# CZ201C_V2_0.net
KiCad netlist of a schematic drawn in Altium Designer
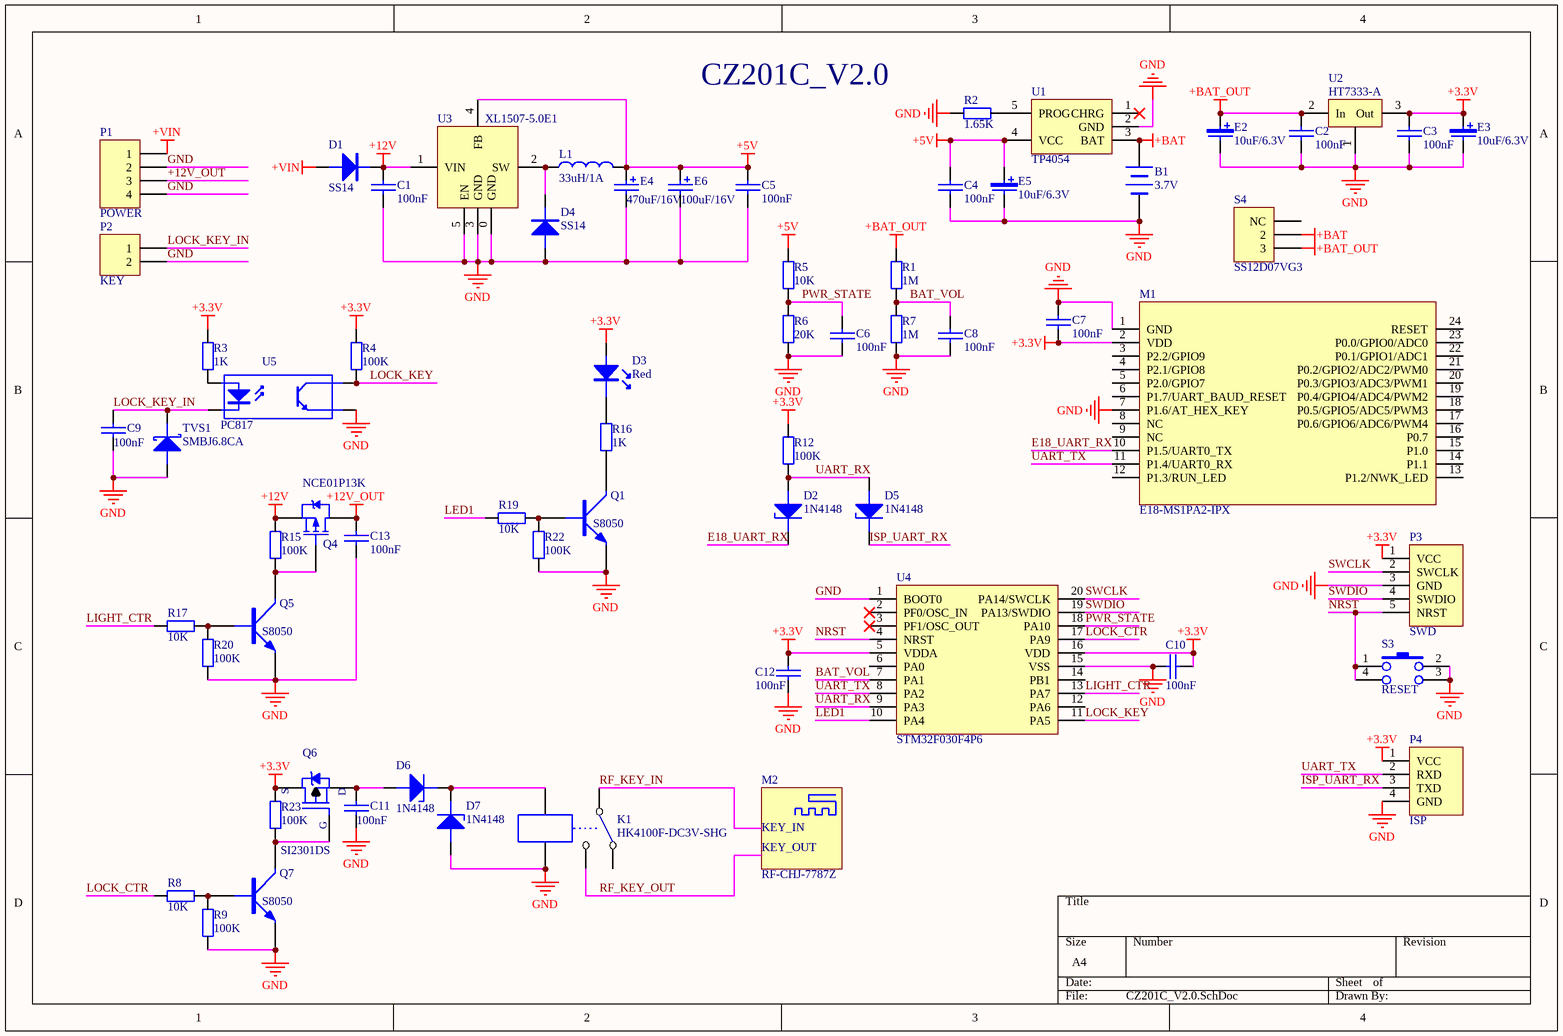
[diagram p0: CZ201C_V2.0.SchDoc]

(export (version "E")
  (design (tool "Eeschema 10.0.6"))
  (components
    (comp (ref "B1")
      (value "3.7V")
      (footprint "Cheng_Interface Unit:XH2.54-2P-BAT")
      (libsource (lib "Cheng_Misc Component") (part "BATTERY"))
    )
    (comp (ref "C1")
      (value "100nF")
      (footprint "Cheng_Resistor_Capacitor:0603_CN")
      (libsource (lib "Cheng_Resistor_Capacitor") (part "Cap1"))
    )
    (comp (ref "C2")
      (value "100nF")
      (footprint "Cheng_Resistor_Capacitor:0603_CN")
      (libsource (lib "Cheng_Resistor_Capacitor") (part "Cap1"))
    )
    (comp (ref "C3")
      (value "100nF")
      (footprint "Cheng_Resistor_Capacitor:0603_CN")
      (libsource (lib "Cheng_Resistor_Capacitor") (part "Cap1"))
    )
    (comp (ref "C4")
      (value "100nF")
      (footprint "Cheng_Resistor_Capacitor:0603_CN")
      (libsource (lib "Cheng_Resistor_Capacitor") (part "Cap1"))
    )
    (comp (ref "C5")
      (value "100nF")
      (footprint "Cheng_Resistor_Capacitor:0603_CN")
      (libsource (lib "Cheng_Resistor_Capacitor") (part "Cap1"))
    )
    (comp (ref "C6")
      (value "100nF")
      (footprint "Cheng_Resistor_Capacitor:0603_CN")
      (libsource (lib "Cheng_Resistor_Capacitor") (part "Cap1"))
    )
    (comp (ref "C7")
      (value "100nF")
      (footprint "Cheng_Resistor_Capacitor:0603_CN")
      (libsource (lib "Cheng_Resistor_Capacitor") (part "Cap1"))
    )
    (comp (ref "C8")
      (value "100nF")
      (footprint "Cheng_Resistor_Capacitor:0603_CN")
      (libsource (lib "Cheng_Resistor_Capacitor") (part "Cap1"))
    )
    (comp (ref "C9")
      (value "100nF")
      (footprint "Cheng_Resistor_Capacitor:0603_CN")
      (libsource (lib "Cheng_Resistor_Capacitor") (part "Cap1"))
    )
    (comp (ref "C10")
      (value "100nF")
      (footprint "Cheng_Resistor_Capacitor:0603_CN")
      (libsource (lib "Cheng_Resistor_Capacitor") (part "Cap1"))
    )
    (comp (ref "C11")
      (value "100nF")
      (footprint "Cheng_Resistor_Capacitor:0603_CN")
      (libsource (lib "Cheng_Resistor_Capacitor") (part "Cap1"))
    )
    (comp (ref "C12")
      (value "100nF")
      (footprint "Cheng_Resistor_Capacitor:0603_CN")
      (libsource (lib "Cheng_Resistor_Capacitor") (part "Cap1"))
    )
    (comp (ref "C13")
      (value "100nF")
      (footprint "Cheng_Resistor_Capacitor:0603_CN")
      (libsource (lib "Cheng_Resistor_Capacitor") (part "Cap1"))
    )
    (comp (ref "D1")
      (value "SS14")
      (footprint "Cheng_Diode_Transistor:DO-214AC(SMA)")
      (libsource (lib "Cheng_Diode_Transistor") (part "Diode-A"))
    )
    (comp (ref "D2")
      (value "1N4148")
      (footprint "Cheng_Diode_Transistor:LL-34")
      (libsource (lib "Cheng_Diode_Transistor") (part "Diode-B"))
    )
    (comp (ref "D3")
      (value "Red")
      (footprint "Cheng_Diode_Transistor:0603_LED")
      (libsource (lib "Cheng_Diode_Transistor") (part "LED"))
    )
    (comp (ref "D4")
      (value "SS14")
      (footprint "Cheng_Diode_Transistor:DO-214AC(SMA)")
      (libsource (lib "Cheng_Diode_Transistor") (part "Diode-A"))
    )
    (comp (ref "D5")
      (value "1N4148")
      (footprint "Cheng_Diode_Transistor:LL-34")
      (libsource (lib "Cheng_Diode_Transistor") (part "Diode-B"))
    )
    (comp (ref "D6")
      (value "1N4148")
      (footprint "Cheng_Diode_Transistor:LL-34")
      (libsource (lib "Cheng_Diode_Transistor") (part "Diode-B"))
    )
    (comp (ref "D7")
      (value "1N4148")
      (footprint "Cheng_Diode_Transistor:LL-34")
      (libsource (lib "Cheng_Diode_Transistor") (part "Diode-B"))
    )
    (comp (ref "E2")
      (value "10uF/6.3V")
      (footprint "Cheng_Resistor_Capacitor:3216_E")
      (libsource (lib "Cheng_Resistor_Capacitor") (part "Cap Ta"))
    )
    (comp (ref "E3")
      (value "10uF/6.3V")
      (footprint "Cheng_Resistor_Capacitor:3216_E")
      (libsource (lib "Cheng_Resistor_Capacitor") (part "Cap Ta"))
    )
    (comp (ref "E4")
      (value "470uF/16V")
      (footprint "Cheng_Resistor_Capacitor:CS_470uF/16V")
      (libsource (lib "Cheng_Resistor_Capacitor") (part "Cap Pol1"))
    )
    (comp (ref "E5")
      (value "10uF/6.3V")
      (footprint "Cheng_Resistor_Capacitor:3216_E")
      (libsource (lib "Cheng_Resistor_Capacitor") (part "Cap Ta"))
    )
    (comp (ref "E6")
      (value "100uF/16V")
      (footprint "Cheng_Resistor_Capacitor:CS_100uF/16V")
      (libsource (lib "Cheng_Resistor_Capacitor") (part "Cap Pol1"))
    )
    (comp (ref "K1")
      (value "HK4100F-DC3V-SHG")
      (footprint "Cheng_Misc Component:HK4100-DC5V-SHG")
      (description "HK4100-DC5V-SHG,HRS1H-S-DC5V")
      (libsource (lib "Cheng_Misc Component") (part "HK4100F-DC5V-SHG"))
    )
    (comp (ref "L1")
      (value "33uH/1A")
      (footprint "Cheng_Resistor_Capacitor:CDRH74")
      (libsource (lib "Cheng_Resistor_Capacitor") (part "Inductor"))
    )
    (comp (ref "M1")
      (value "E18-MS1PA2-IPX")
      (footprint "Cheng_Module:E18-MS1PA2-IPX")
      (libsource (lib "Cheng_Module") (part "E18-MS1PA2-IPX"))
    )
    (comp (ref "M2")
      (value "RF-CHJ-7787Z")
      (footprint "Cheng_Module:RF-CHJ-7787Z")
      (libsource (lib "Cheng_Module") (part "RF-CHJ-7787Z"))
    )
    (comp (ref "P1")
      (value "POWER")
      (footprint "Cheng_Interface Unit:KF3.5-4P")
      (description "Header, 4-Pin")
      (fields (field (name "PUBLISHER") "Altium Limited"))
      (libsource (lib "Cheng_Interface Unit") (part "Header 4"))
    )
    (comp (ref "P2")
      (value "KEY")
      (footprint "Cheng_Interface Unit:KF3.5-2P")
      (description "Header, 2-Pin")
      (fields (field (name "PUBLISHER") "Altium Limited"))
      (libsource (lib "Cheng_Interface Unit") (part "Header 2"))
    )
    (comp (ref "P3")
      (value "SWD")
      (footprint "Cheng_Interface Unit:XH2.54-5P")
      (libsource (lib "Cheng_Interface Unit") (part "SWD"))
    )
    (comp (ref "P4")
      (value "ISP")
      (footprint "Cheng_Interface Unit:XH2.54-4P")
      (libsource (lib "Cheng_Interface Unit") (part "ISP_UART"))
    )
    (comp (ref "Q1")
      (value "S8050")
      (footprint "Cheng_Diode_Transistor:SOT-23")
      (libsource (lib "Cheng_Diode_Transistor") (part "8050"))
    )
    (comp (ref "Q4")
      (value "NCE01P13K")
      (footprint "Cheng_Manostat:TO-252")
      (description "P-Channel Power MOSFET")
      (fields (field (name "PUBLISHER") "Altium Limited"))
      (libsource (lib "Miscellaneous Devices") (part "PMOS-2"))
    )
    (comp (ref "Q5")
      (value "S8050")
      (footprint "Cheng_Diode_Transistor:SOT-23")
      (libsource (lib "Cheng_Diode_Transistor") (part "8050"))
    )
    (comp (ref "Q6")
      (value "SI2301DS")
      (footprint "Cheng_Diode_Transistor:SOT-23")
      (libsource (lib "Cheng_Diode_Transistor") (part "MOSFET P"))
    )
    (comp (ref "Q7")
      (value "S8050")
      (footprint "Cheng_Diode_Transistor:SOT-23")
      (libsource (lib "Cheng_Diode_Transistor") (part "8050"))
    )
    (comp (ref "R1")
      (value "1M")
      (footprint "Cheng_Resistor_Capacitor:0603_RN")
      (libsource (lib "") (part "Res1_1"))
    )
    (comp (ref "R2")
      (value "1.65K")
      (footprint "Cheng_Resistor_Capacitor:0603_RN")
      (libsource (lib "Cheng_Resistor_Capacitor") (part "Res1"))
    )
    (comp (ref "R3")
      (value "1K")
      (footprint "Cheng_Resistor_Capacitor:0603_RN")
      (libsource (lib "") (part "Res1_1"))
    )
    (comp (ref "R4")
      (value "100K")
      (footprint "Cheng_Resistor_Capacitor:0603_RN")
      (libsource (lib "") (part "Res1_1"))
    )
    (comp (ref "R5")
      (value "10K")
      (footprint "Cheng_Resistor_Capacitor:0603_RN")
      (libsource (lib "") (part "Res1_1"))
    )
    (comp (ref "R6")
      (value "20K")
      (footprint "Cheng_Resistor_Capacitor:0603_RN")
      (libsource (lib "") (part "Res1_1"))
    )
    (comp (ref "R7")
      (value "1M")
      (footprint "Cheng_Resistor_Capacitor:0603_RN")
      (libsource (lib "") (part "Res1_1"))
    )
    (comp (ref "R8")
      (value "10K")
      (footprint "Cheng_Resistor_Capacitor:0603_RN")
      (libsource (lib "") (part "Res1_2"))
    )
    (comp (ref "R9")
      (value "100K")
      (footprint "Cheng_Resistor_Capacitor:0603_RN")
      (libsource (lib "") (part "Res1_1"))
    )
    (comp (ref "R12")
      (value "100K")
      (footprint "Cheng_Resistor_Capacitor:0603_RN")
      (libsource (lib "") (part "Res1_1"))
    )
    (comp (ref "R15")
      (value "100K")
      (footprint "Cheng_Resistor_Capacitor:0603_RN")
      (libsource (lib "") (part "Res1_1"))
    )
    (comp (ref "R16")
      (value "1K")
      (footprint "Cheng_Resistor_Capacitor:0603_RN")
      (libsource (lib "") (part "Res1_1"))
    )
    (comp (ref "R17")
      (value "10K")
      (footprint "Cheng_Resistor_Capacitor:0603_RN")
      (libsource (lib "Cheng_Resistor_Capacitor") (part "Res1"))
    )
    (comp (ref "R19")
      (value "10K")
      (footprint "Cheng_Resistor_Capacitor:0603_RN")
      (libsource (lib "") (part "Res1_2"))
    )
    (comp (ref "R20")
      (value "100K")
      (footprint "Cheng_Resistor_Capacitor:0603_RN")
      (libsource (lib "") (part "Res1_1"))
    )
    (comp (ref "R22")
      (value "100K")
      (footprint "Cheng_Resistor_Capacitor:0603_RN")
      (libsource (lib "") (part "Res1_1"))
    )
    (comp (ref "R23")
      (value "100K")
      (footprint "Cheng_Resistor_Capacitor:0603_RN")
      (libsource (lib "") (part "Res1_1"))
    )
    (comp (ref "S3")
      (value "RESET")
      (footprint "Cheng_Misc Component:KEY-6*6MM-DIP")
      (libsource (lib "Cheng_Misc Component") (part "SW-4"))
    )
    (comp (ref "S4")
      (value "SS12D07VG3")
      (footprint "Cheng_Misc Component:SS-12D07G3")
      (libsource (lib "Cheng_Misc Component") (part "SS-12D07G3"))
    )
    (comp (ref "TVS1")
      (value "SMBJ6.8CA")
      (footprint "Cheng_Diode_Transistor:DO-214AA(SMB)")
      (libsource (lib "Cheng_Diode_Transistor") (part "Diode-C"))
    )
    (comp (ref "U1")
      (value "TP4054")
      (footprint "Cheng_Diode_Transistor:SOT-23-5")
      (description "TP4054,LTC4054 ,PJ4054MR")
      (libsource (lib "Cheng_IC") (part "QX4054"))
    )
    (comp (ref "U2")
      (value "HT7333-A")
      (footprint "SOT-89")
      (description "HT7533; Output 500mA; Iq: 5uA, max= 7uA")
      (libsource (lib "Cheng_Manostat") (part "HT7833"))
    )
    (comp (ref "U3")
      (value "XL1507-5.0E1")
      (footprint "Cheng_Manostat:TO-252-5")
      (libsource (lib "Cheng_Manostat") (part "XL1507"))
    )
    (comp (ref "U4")
      (value "STM32F030F4P6")
      (footprint "Cheng_IC:TSSOP20")
      (libsource (lib "Cheng_STM32") (part "STM32F030F4P6"))
    )
    (comp (ref "U5")
      (value "PC817")
      (footprint "Cheng_IC:SOP-4")
      (libsource (lib "Cheng_Diode_Transistor") (part "PC817"))
    )
  )
  (nets
    (net (code "1") (name "+3.3V") (class "Default")
      (node (ref "C10") (pin "1") (pinfunction "1_1") (pintype "passive"))
      (node (ref "C12") (pin "1") (pinfunction "1_1") (pintype "passive"))
      (node (ref "C3") (pin "1") (pinfunction "1_1") (pintype "passive"))
      (node (ref "C7") (pin "2") (pinfunction "2_2") (pintype "passive"))
      (node (ref "D3") (pin "A") (pinfunction "1_A") (pintype "passive"))
      (node (ref "E3") (pin "1") (pinfunction "1_1") (pintype "passive"))
      (node (ref "M1") (pin "2") (pinfunction "VDD_2") (pintype "passive"))
      (node (ref "P3") (pin "1") (pinfunction "VCC_1") (pintype "passive"))
      (node (ref "P4") (pin "1") (pinfunction "VCC_1") (pintype "passive"))
      (node (ref "Q6") (pin "2") (pinfunction "S_2") (pintype "passive"))
      (node (ref "R12") (pin "2") (pinfunction "2_2") (pintype "passive"))
      (node (ref "R23") (pin "2") (pinfunction "2_2") (pintype "passive"))
      (node (ref "R3") (pin "2") (pinfunction "2_2") (pintype "passive"))
      (node (ref "R4") (pin "2") (pinfunction "2_2") (pintype "passive"))
      (node (ref "U2") (pin "3") (pinfunction "Out_3") (pintype "passive"))
      (node (ref "U4") (pin "16") (pinfunction "VDD_16") (pintype "passive"))
      (node (ref "U4") (pin "5") (pinfunction "VDDA_5") (pintype "passive"))
    )
    (net (code "2") (name "+5V") (class "Default")
      (node (ref "C4") (pin "1") (pinfunction "1_1") (pintype "passive"))
      (node (ref "C5") (pin "1") (pinfunction "1_1") (pintype "passive"))
      (node (ref "E4") (pin "1") (pinfunction "1_1") (pintype "passive"))
      (node (ref "E5") (pin "1") (pinfunction "1_1") (pintype "passive"))
      (node (ref "E6") (pin "1") (pinfunction "1_1") (pintype "passive"))
      (node (ref "L1") (pin "2") (pinfunction "2_2") (pintype "passive"))
      (node (ref "R5") (pin "2") (pinfunction "2_2") (pintype "passive"))
      (node (ref "U1") (pin "4") (pinfunction "VCC_4") (pintype "power_in"))
      (node (ref "U3") (pin "4") (pinfunction "FB_4") (pintype "passive"))
    )
    (net (code "3") (name "+12V") (class "Default")
      (node (ref "C1") (pin "1") (pinfunction "1_1") (pintype "passive"))
      (node (ref "D1") (pin "K") (pinfunction "2_K") (pintype "passive"))
      (node (ref "Q4") (pin "3") (pinfunction "S_3") (pintype "passive"))
      (node (ref "R15") (pin "2") (pinfunction "2_2") (pintype "passive"))
      (node (ref "U3") (pin "1") (pinfunction "VIN_1") (pintype "passive"))
    )
    (net (code "4") (name "+12V_OUT") (class "Default")
      (node (ref "C13") (pin "1") (pinfunction "1_1") (pintype "passive"))
      (node (ref "P1") (pin "3") (pinfunction "3_3") (pintype "passive"))
      (node (ref "Q4") (pin "2") (pinfunction "D_2") (pintype "passive"))
    )
    (net (code "5") (name "+BAT") (class "Default")
      (node (ref "B1") (pin "1") (pinfunction "+_1") (pintype "passive"))
      (node (ref "S4") (pin "2") (pinfunction "2_2") (pintype "passive"))
      (node (ref "U1") (pin "3") (pinfunction "BAT_3") (pintype "passive"))
    )
    (net (code "6") (name "+BAT_OUT") (class "Default")
      (node (ref "C2") (pin "1") (pinfunction "1_1") (pintype "passive"))
      (node (ref "E2") (pin "1") (pinfunction "1_1") (pintype "passive"))
      (node (ref "R1") (pin "2") (pinfunction "2_2") (pintype "passive"))
      (node (ref "S4") (pin "3") (pinfunction "3_3") (pintype "passive"))
      (node (ref "U2") (pin "2") (pinfunction "In_2") (pintype "passive"))
    )
    (net (code "7") (name "+VIN") (class "Default")
      (node (ref "D1") (pin "A") (pinfunction "1_A") (pintype "passive"))
      (node (ref "P1") (pin "1") (pinfunction "1_1") (pintype "passive"))
    )
    (net (code "8") (name "/BAT_VOL") (class "Default")
      (node (ref "C8") (pin "1") (pinfunction "1_1") (pintype "passive"))
      (node (ref "R1") (pin "1") (pinfunction "1_1") (pintype "passive"))
      (node (ref "R7") (pin "2") (pinfunction "2_2") (pintype "passive"))
      (node (ref "U4") (pin "7") (pinfunction "PA1_7") (pintype "passive"))
    )
    (net (code "9") (name "/E18_UART_RX") (class "Default")
      (node (ref "D2") (pin "K") (pinfunction "2_K") (pintype "passive"))
      (node (ref "M1") (pin "10") (pinfunction "P1.5/UART0_TX_10") (pintype "passive"))
    )
    (net (code "10") (name "/ISP_UART_RX") (class "Default")
      (node (ref "D5") (pin "K") (pinfunction "2_K") (pintype "passive"))
      (node (ref "P4") (pin "3") (pinfunction "TXD_3") (pintype "passive"))
    )
    (net (code "11") (name "/LED1") (class "Default")
      (node (ref "R19") (pin "2") (pinfunction "2_2") (pintype "passive"))
      (node (ref "U4") (pin "10") (pinfunction "PA4_10") (pintype "passive"))
    )
    (net (code "12") (name "/LIGHT_CTR") (class "Default")
      (node (ref "R17") (pin "1") (pinfunction "1_1") (pintype "passive"))
      (node (ref "U4") (pin "13") (pinfunction "PA7_13") (pintype "passive"))
    )
    (net (code "13") (name "/LOCK_CTR") (class "Default")
      (node (ref "R8") (pin "2") (pinfunction "2_2") (pintype "passive"))
      (node (ref "U4") (pin "17") (pinfunction "PA9_17") (pintype "passive"))
    )
    (net (code "14") (name "/LOCK_KEY") (class "Default")
      (node (ref "R4") (pin "1") (pinfunction "1_1") (pintype "passive"))
      (node (ref "U4") (pin "11") (pinfunction "PA5_11") (pintype "passive"))
      (node (ref "U5") (pin "4") (pinfunction "C_4") (pintype "passive"))
    )
    (net (code "15") (name "/LOCK_KEY_IN") (class "Default")
      (node (ref "C9") (pin "1") (pinfunction "1_1") (pintype "passive"))
      (node (ref "P2") (pin "1") (pinfunction "1_1") (pintype "passive"))
      (node (ref "TVS1") (pin "K") (pinfunction "2_K") (pintype "passive"))
      (node (ref "U5") (pin "2") (pinfunction "K_2") (pintype "passive"))
    )
    (net (code "16") (name "/NRST") (class "Default")
      (node (ref "P3") (pin "5") (pinfunction "NRST_5") (pintype "passive"))
      (node (ref "S3") (pin "1") (pinfunction "1_1") (pintype "passive"))
      (node (ref "S3") (pin "4") (pinfunction "4_4") (pintype "passive"))
      (node (ref "U4") (pin "4") (pinfunction "NRST_4") (pintype "passive"))
    )
    (net (code "17") (name "/PWR_STATE") (class "Default")
      (node (ref "C6") (pin "1") (pinfunction "1_1") (pintype "passive"))
      (node (ref "R5") (pin "1") (pinfunction "1_1") (pintype "passive"))
      (node (ref "R6") (pin "2") (pinfunction "2_2") (pintype "passive"))
      (node (ref "U4") (pin "18") (pinfunction "PA10_18") (pintype "passive"))
    )
    (net (code "18") (name "/RF_KEY_IN") (class "Default")
      (node (ref "K1") (pin "1") (pinfunction "1_1") (pintype "passive"))
    )
    (net (code "19") (name "/RF_KEY_OUT") (class "Default")
      (node (ref "K1") (pin "3") (pinfunction "3_3") (pintype "passive"))
    )
    (net (code "20") (name "/SWCLK") (class "Default")
      (node (ref "P3") (pin "2") (pinfunction "SWCLK_2") (pintype "passive"))
      (node (ref "U4") (pin "20") (pinfunction "PA14/SWCLK_20") (pintype "passive"))
    )
    (net (code "21") (name "/SWDIO") (class "Default")
      (node (ref "P3") (pin "4") (pinfunction "SWDIO_4") (pintype "passive"))
      (node (ref "U4") (pin "19") (pinfunction "PA13/SWDIO_19") (pintype "passive"))
    )
    (net (code "22") (name "/UART_RX") (class "Default")
      (node (ref "D2") (pin "A") (pinfunction "1_A") (pintype "passive"))
      (node (ref "D5") (pin "A") (pinfunction "1_A") (pintype "passive"))
      (node (ref "R12") (pin "1") (pinfunction "1_1") (pintype "passive"))
      (node (ref "U4") (pin "9") (pinfunction "PA3_9") (pintype "passive"))
    )
    (net (code "23") (name "/UART_TX") (class "Default")
      (node (ref "M1") (pin "11") (pinfunction "P1.4/UART0_RX_11") (pintype "passive"))
      (node (ref "P4") (pin "2") (pinfunction "RXD_2") (pintype "passive"))
      (node (ref "U4") (pin "8") (pinfunction "PA2_8") (pintype "passive"))
    )
    (net (code "24") (name "GND") (class "Default")
      (node (ref "B1") (pin "2") (pinfunction "-_2") (pintype "passive"))
      (node (ref "C1") (pin "2") (pinfunction "2_2") (pintype "passive"))
      (node (ref "C10") (pin "2") (pinfunction "2_2") (pintype "passive"))
      (node (ref "C11") (pin "2") (pinfunction "2_2") (pintype "passive"))
      (node (ref "C12") (pin "2") (pinfunction "2_2") (pintype "passive"))
      (node (ref "C13") (pin "2") (pinfunction "2_2") (pintype "passive"))
      (node (ref "C2") (pin "2") (pinfunction "2_2") (pintype "passive"))
      (node (ref "C3") (pin "2") (pinfunction "2_2") (pintype "passive"))
      (node (ref "C4") (pin "2") (pinfunction "2_2") (pintype "passive"))
      (node (ref "C5") (pin "2") (pinfunction "2_2") (pintype "passive"))
      (node (ref "C6") (pin "2") (pinfunction "2_2") (pintype "passive"))
      (node (ref "C7") (pin "1") (pinfunction "1_1") (pintype "passive"))
      (node (ref "C8") (pin "2") (pinfunction "2_2") (pintype "passive"))
      (node (ref "C9") (pin "2") (pinfunction "2_2") (pintype "passive"))
      (node (ref "D4") (pin "A") (pinfunction "1_A") (pintype "passive"))
      (node (ref "D7") (pin "A") (pinfunction "1_A") (pintype "passive"))
      (node (ref "E2") (pin "2") (pinfunction "2_2") (pintype "passive"))
      (node (ref "E3") (pin "2") (pinfunction "2_2") (pintype "passive"))
      (node (ref "E4") (pin "2") (pinfunction "2_2") (pintype "passive"))
      (node (ref "E5") (pin "2") (pinfunction "2_2") (pintype "passive"))
      (node (ref "E6") (pin "2") (pinfunction "2_2") (pintype "passive"))
      (node (ref "K1") (pin "5") (pinfunction "5_5") (pintype "passive"))
      (node (ref "M1") (pin "1") (pinfunction "GND_1") (pintype "passive"))
      (node (ref "M1") (pin "7") (pinfunction "P1.6/AT_HEX_KEY_7") (pintype "passive"))
      (node (ref "P1") (pin "2") (pinfunction "2_2") (pintype "passive"))
      (node (ref "P1") (pin "4") (pinfunction "4_4") (pintype "passive"))
      (node (ref "P2") (pin "2") (pinfunction "2_2") (pintype "passive"))
      (node (ref "P3") (pin "3") (pinfunction "GND_3") (pintype "passive"))
      (node (ref "P4") (pin "4") (pinfunction "GND_4") (pintype "passive"))
      (node (ref "Q1") (pin "2") (pinfunction "E_2") (pintype "passive"))
      (node (ref "Q5") (pin "2") (pinfunction "E_2") (pintype "passive"))
      (node (ref "Q7") (pin "2") (pinfunction "E_2") (pintype "passive"))
      (node (ref "R2") (pin "1") (pinfunction "1_1") (pintype "passive"))
      (node (ref "R20") (pin "1") (pinfunction "1_1") (pintype "passive"))
      (node (ref "R22") (pin "1") (pinfunction "1_1") (pintype "passive"))
      (node (ref "R6") (pin "1") (pinfunction "1_1") (pintype "passive"))
      (node (ref "R7") (pin "1") (pinfunction "1_1") (pintype "passive"))
      (node (ref "R9") (pin "1") (pinfunction "1_1") (pintype "passive"))
      (node (ref "S3") (pin "2") (pinfunction "2_2") (pintype "passive"))
      (node (ref "S3") (pin "3") (pinfunction "3_3") (pintype "passive"))
      (node (ref "TVS1") (pin "A") (pinfunction "1_A") (pintype "passive"))
      (node (ref "U1") (pin "2") (pinfunction "GND_2") (pintype "passive"))
      (node (ref "U2") (pin "1") (pinfunction "GND_1") (pintype "passive"))
      (node (ref "U3") (pin "0") (pinfunction "GND_0") (pintype "passive"))
      (node (ref "U3") (pin "3") (pinfunction "GND_3") (pintype "passive"))
      (node (ref "U3") (pin "5") (pinfunction "EN_5") (pintype "passive"))
      (node (ref "U4") (pin "1") (pinfunction "BOOT0_1") (pintype "passive"))
      (node (ref "U4") (pin "15") (pinfunction "VSS_15") (pintype "passive"))
      (node (ref "U5") (pin "3") (pinfunction "E_3") (pintype "passive"))
    )
    (net (code "25") (name "Net-(D3-2)") (class "Default")
      (node (ref "D3") (pin "K") (pinfunction "2_K") (pintype "passive"))
      (node (ref "R16") (pin "2") (pinfunction "2_2") (pintype "passive"))
    )
    (net (code "26") (name "Net-(D4-2)") (class "Default")
      (node (ref "D4") (pin "K") (pinfunction "2_K") (pintype "passive"))
      (node (ref "L1") (pin "1") (pinfunction "1_1") (pintype "passive"))
      (node (ref "U3") (pin "2") (pinfunction "SW_2") (pintype "passive"))
    )
    (net (code "27") (name "Net-(D6-1)") (class "Default")
      (node (ref "C11") (pin "1") (pinfunction "1_1") (pintype "passive"))
      (node (ref "D6") (pin "A") (pinfunction "1_A") (pintype "passive"))
      (node (ref "Q6") (pin "3") (pinfunction "D_3") (pintype "passive"))
    )
    (net (code "28") (name "Net-(D6-2)") (class "Default")
      (node (ref "D6") (pin "K") (pinfunction "2_K") (pintype "passive"))
      (node (ref "D7") (pin "K") (pinfunction "2_K") (pintype "passive"))
      (node (ref "K1") (pin "4") (pinfunction "4_4") (pintype "passive"))
    )
    (net (code "29") (name "Net-(Q1-B)") (class "Default")
      (node (ref "Q1") (pin "1") (pinfunction "B_1") (pintype "passive"))
      (node (ref "R19") (pin "1") (pinfunction "1_1") (pintype "passive"))
      (node (ref "R22") (pin "2") (pinfunction "2_2") (pintype "passive"))
    )
    (net (code "30") (name "Net-(Q1-C)") (class "Default")
      (node (ref "Q1") (pin "3") (pinfunction "C_3") (pintype "passive"))
      (node (ref "R16") (pin "1") (pinfunction "1_1") (pintype "passive"))
    )
    (net (code "31") (name "Net-(Q4-G)") (class "Default")
      (node (ref "Q4") (pin "1") (pinfunction "G_1") (pintype "passive"))
      (node (ref "Q5") (pin "3") (pinfunction "C_3") (pintype "passive"))
      (node (ref "R15") (pin "1") (pinfunction "1_1") (pintype "passive"))
    )
    (net (code "32") (name "Net-(Q5-B)") (class "Default")
      (node (ref "Q5") (pin "1") (pinfunction "B_1") (pintype "passive"))
      (node (ref "R17") (pin "2") (pinfunction "2_2") (pintype "passive"))
      (node (ref "R20") (pin "2") (pinfunction "2_2") (pintype "passive"))
    )
    (net (code "33") (name "Net-(Q6-G)") (class "Default")
      (node (ref "Q6") (pin "1") (pinfunction "G_1") (pintype "passive"))
      (node (ref "Q7") (pin "3") (pinfunction "C_3") (pintype "passive"))
      (node (ref "R23") (pin "1") (pinfunction "1_1") (pintype "passive"))
    )
    (net (code "34") (name "Net-(Q7-B)") (class "Default")
      (node (ref "Q7") (pin "1") (pinfunction "B_1") (pintype "passive"))
      (node (ref "R8") (pin "1") (pinfunction "1_1") (pintype "passive"))
      (node (ref "R9") (pin "2") (pinfunction "2_2") (pintype "passive"))
    )
    (net (code "35") (name "Net-(U1-PROG)") (class "Default")
      (node (ref "R2") (pin "2") (pinfunction "2_2") (pintype "passive"))
      (node (ref "U1") (pin "5") (pinfunction "PROG_5") (pintype "passive"))
    )
    (net (code "36") (name "Net-(U5-A)") (class "Default")
      (node (ref "R3") (pin "1") (pinfunction "1_1") (pintype "passive"))
      (node (ref "U5") (pin "1") (pinfunction "A_1") (pintype "passive"))
    )
    (net (code "37") (name "unconnected-(K1-Pad2)") (class "Default")
      (node (ref "K1") (pin "2") (pinfunction "2_2") (pintype "passive"))
    )
    (net (code "38") (name "unconnected-(M1-NC-Pad8)") (class "Default")
      (node (ref "M1") (pin "8") (pinfunction "NC_8") (pintype "passive"))
    )
    (net (code "39") (name "unconnected-(M1-NC-Pad9)") (class "Default")
      (node (ref "M1") (pin "9") (pinfunction "NC_9") (pintype "passive"))
    )
    (net (code "40") (name "unconnected-(M1-P0.0{slash}GPIO0{slash}ADC0-Pad23)") (class "Default")
      (node (ref "M1") (pin "23") (pinfunction "P0.0/GPIO0/ADC0_23") (pintype "passive"))
    )
    (net (code "41") (name "unconnected-(M1-P0.1{slash}GPIO1{slash}ADC1-Pad22)") (class "Default")
      (node (ref "M1") (pin "22") (pinfunction "P0.1/GPIO1/ADC1_22") (pintype "passive"))
    )
    (net (code "42") (name "unconnected-(M1-P0.2{slash}GPIO2{slash}ADC2{slash}PWM0-Pad21)") (class "Default")
      (node (ref "M1") (pin "21") (pinfunction "P0.2/GPIO2/ADC2/PWM0_21") (pintype "passive"))
    )
    (net (code "43") (name "unconnected-(M1-P0.3{slash}GPIO3{slash}ADC3{slash}PWM1-Pad20)") (class "Default")
      (node (ref "M1") (pin "20") (pinfunction "P0.3/GPIO3/ADC3/PWM1_20") (pintype "passive"))
    )
    (net (code "44") (name "unconnected-(M1-P0.4{slash}GPIO4{slash}ADC4{slash}PWM2-Pad19)") (class "Default")
      (node (ref "M1") (pin "19") (pinfunction "P0.4/GPIO4/ADC4/PWM2_19") (pintype "passive"))
    )
    (net (code "45") (name "unconnected-(M1-P0.5{slash}GPIO5{slash}ADC5{slash}PWM3-Pad18)") (class "Default")
      (node (ref "M1") (pin "18") (pinfunction "P0.5/GPIO5/ADC5/PWM3_18") (pintype "passive"))
    )
    (net (code "46") (name "unconnected-(M1-P0.6{slash}GPIO6{slash}ADC6{slash}PWM4-Pad17)") (class "Default")
      (node (ref "M1") (pin "17") (pinfunction "P0.6/GPIO6/ADC6/PWM4_17") (pintype "passive"))
    )
    (net (code "47") (name "unconnected-(M1-P0.7-Pad16)") (class "Default")
      (node (ref "M1") (pin "16") (pinfunction "P0.7_16") (pintype "passive"))
    )
    (net (code "48") (name "unconnected-(M1-P1.0-Pad15)") (class "Default")
      (node (ref "M1") (pin "15") (pinfunction "P1.0_15") (pintype "passive"))
    )
    (net (code "49") (name "unconnected-(M1-P1.1-Pad14)") (class "Default")
      (node (ref "M1") (pin "14") (pinfunction "P1.1_14") (pintype "passive"))
    )
    (net (code "50") (name "unconnected-(M1-P1.2{slash}NWK_LED-Pad13)") (class "Default")
      (node (ref "M1") (pin "13") (pinfunction "P1.2/NWK_LED_13") (pintype "passive"))
    )
    (net (code "51") (name "unconnected-(M1-P1.3{slash}RUN_LED-Pad12)") (class "Default")
      (node (ref "M1") (pin "12") (pinfunction "P1.3/RUN_LED_12") (pintype "passive"))
    )
    (net (code "52") (name "unconnected-(M1-P1.7{slash}UART_BAUD_RESET-Pad6)") (class "Default")
      (node (ref "M1") (pin "6") (pinfunction "P1.7/UART_BAUD_RESET_6") (pintype "passive"))
    )
    (net (code "53") (name "unconnected-(M1-P2.0{slash}GPIO7-Pad5)") (class "Default")
      (node (ref "M1") (pin "5") (pinfunction "P2.0/GPIO7_5") (pintype "passive"))
    )
    (net (code "54") (name "unconnected-(M1-P2.1{slash}GPIO8-Pad4)") (class "Default")
      (node (ref "M1") (pin "4") (pinfunction "P2.1/GPIO8_4") (pintype "passive"))
    )
    (net (code "55") (name "unconnected-(M1-P2.2{slash}GPIO9-Pad3)") (class "Default")
      (node (ref "M1") (pin "3") (pinfunction "P2.2/GPIO9_3") (pintype "passive"))
    )
    (net (code "56") (name "unconnected-(M1-RESET-Pad24)") (class "Default")
      (node (ref "M1") (pin "24") (pinfunction "RESET_24") (pintype "passive"))
    )
    (net (code "57") (name "unconnected-(S4-NC-Pad1)") (class "Default")
      (node (ref "S4") (pin "1") (pinfunction "NC_1") (pintype "passive"))
    )
    (net (code "58") (name "unconnected-(U1-CHRG-Pad1)") (class "Default")
      (node (ref "U1") (pin "1") (pinfunction "CHRG_1") (pintype "passive+no_connect"))
    )
    (net (code "59") (name "unconnected-(U4-PA0-Pad6)") (class "Default")
      (node (ref "U4") (pin "6") (pinfunction "PA0_6") (pintype "passive"))
    )
    (net (code "60") (name "unconnected-(U4-PA6-Pad12)") (class "Default")
      (node (ref "U4") (pin "12") (pinfunction "PA6_12") (pintype "passive"))
    )
    (net (code "61") (name "unconnected-(U4-PB1-Pad14)") (class "Default")
      (node (ref "U4") (pin "14") (pinfunction "PB1_14") (pintype "passive"))
    )
    (net (code "62") (name "unconnected-(U4-PF0{slash}OSC_IN-Pad2)") (class "Default")
      (node (ref "U4") (pin "2") (pinfunction "PF0/OSC_IN_2") (pintype "passive+no_connect"))
    )
    (net (code "63") (name "unconnected-(U4-PF1{slash}OSC_OUT-Pad3)") (class "Default")
      (node (ref "U4") (pin "3") (pinfunction "PF1/OSC_OUT_3") (pintype "passive+no_connect"))
    )
  )
)
